# 1_8V_Regler.net
KiCad netlist of a schematic drawn in EAGLE
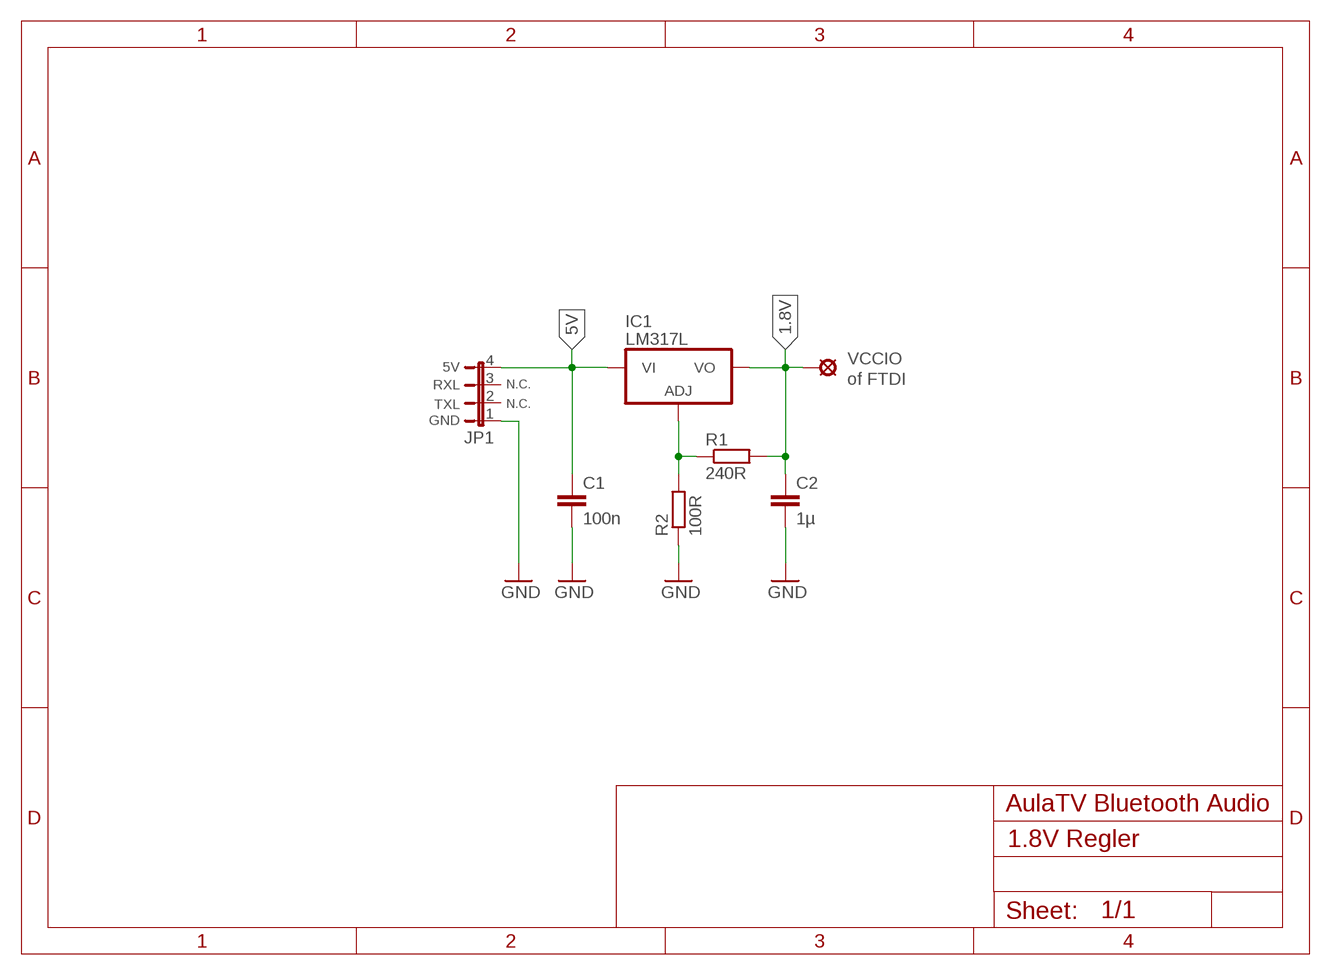
[diagram p0: schematic, sheet 1]

(export (version "E")
  (design (tool "Eeschema 10.0.6"))
  (components
    (comp (ref "C1")
      (value "100n")
      (footprint "eagle-import:C0805")
      (libsource (lib "eagle-import") (part "C-EUC0805"))
    )
    (comp (ref "C2")
      (value "1µ")
      (footprint "eagle-import:C0805")
      (libsource (lib "eagle-import") (part "C-EUC0805"))
    )
    (comp (ref "IC1")
      (value "LM317L")
      (footprint "eagle-import:TO92TAPE")
      (libsource (lib "eagle-import") (part "LM317L"))
    )
    (comp (ref "JP1")
      (value "JP4E")
      (footprint "eagle-import:JP4")
      (libsource (lib "eagle-import") (part "JP4E"))
    )
    (comp (ref "R1")
      (value "240R")
      (footprint "eagle-import:R0805")
      (libsource (lib "eagle-import") (part "R-EU_R0805"))
    )
    (comp (ref "R2")
      (value "100R")
      (footprint "eagle-import:R0805")
      (libsource (lib "eagle-import") (part "R-EU_R0805"))
    )
    (comp (ref "VCCIO")
      (value "VCCIO")
      (footprint "eagle-import:LSP10")
      (libsource (lib "eagle-import") (part "LSP10"))
    )
  )
  (nets
    (net (code "1") (name "1.8V") (class "Default")
      (node (ref "C2") (pin "1") (pinfunction "1_1") (pintype "passive"))
      (node (ref "IC1") (pin "P$3") (pinfunction "VO_P$3") (pintype "passive"))
      (node (ref "R1") (pin "2") (pinfunction "2_2") (pintype "passive"))
      (node (ref "VCCIO") (pin "MP") (pinfunction "MP_MP") (pintype "passive"))
    )
    (net (code "2") (name "5V") (class "Default")
      (node (ref "C1") (pin "1") (pinfunction "1_1") (pintype "passive"))
      (node (ref "IC1") (pin "P$2") (pinfunction "VI_P$2") (pintype "input"))
      (node (ref "JP1") (pin "4") (pinfunction "4_4") (pintype "passive"))
    )
    (net (code "3") (name "GND") (class "Default")
      (node (ref "C1") (pin "2") (pinfunction "2_2") (pintype "passive"))
      (node (ref "C2") (pin "2") (pinfunction "2_2") (pintype "passive"))
      (node (ref "JP1") (pin "1") (pinfunction "1_1") (pintype "passive"))
      (node (ref "R2") (pin "1") (pinfunction "1_1") (pintype "passive"))
    )
    (net (code "4") (name "Net-(IC1-ADJ)") (class "Default")
      (node (ref "IC1") (pin "P$1") (pinfunction "ADJ_P$1") (pintype "input"))
      (node (ref "R1") (pin "1") (pinfunction "1_1") (pintype "passive"))
      (node (ref "R2") (pin "2") (pinfunction "2_2") (pintype "passive"))
    )
    (net (code "5") (name "unconnected-(JP1-Pad2)") (class "Default")
      (node (ref "JP1") (pin "2") (pinfunction "2_2") (pintype "passive"))
    )
    (net (code "6") (name "unconnected-(JP1-Pad3)") (class "Default")
      (node (ref "JP1") (pin "3") (pinfunction "3_3") (pintype "passive"))
    )
  )
)
